# schematic.net
KiCad netlist of a schematic drawn in EAGLE
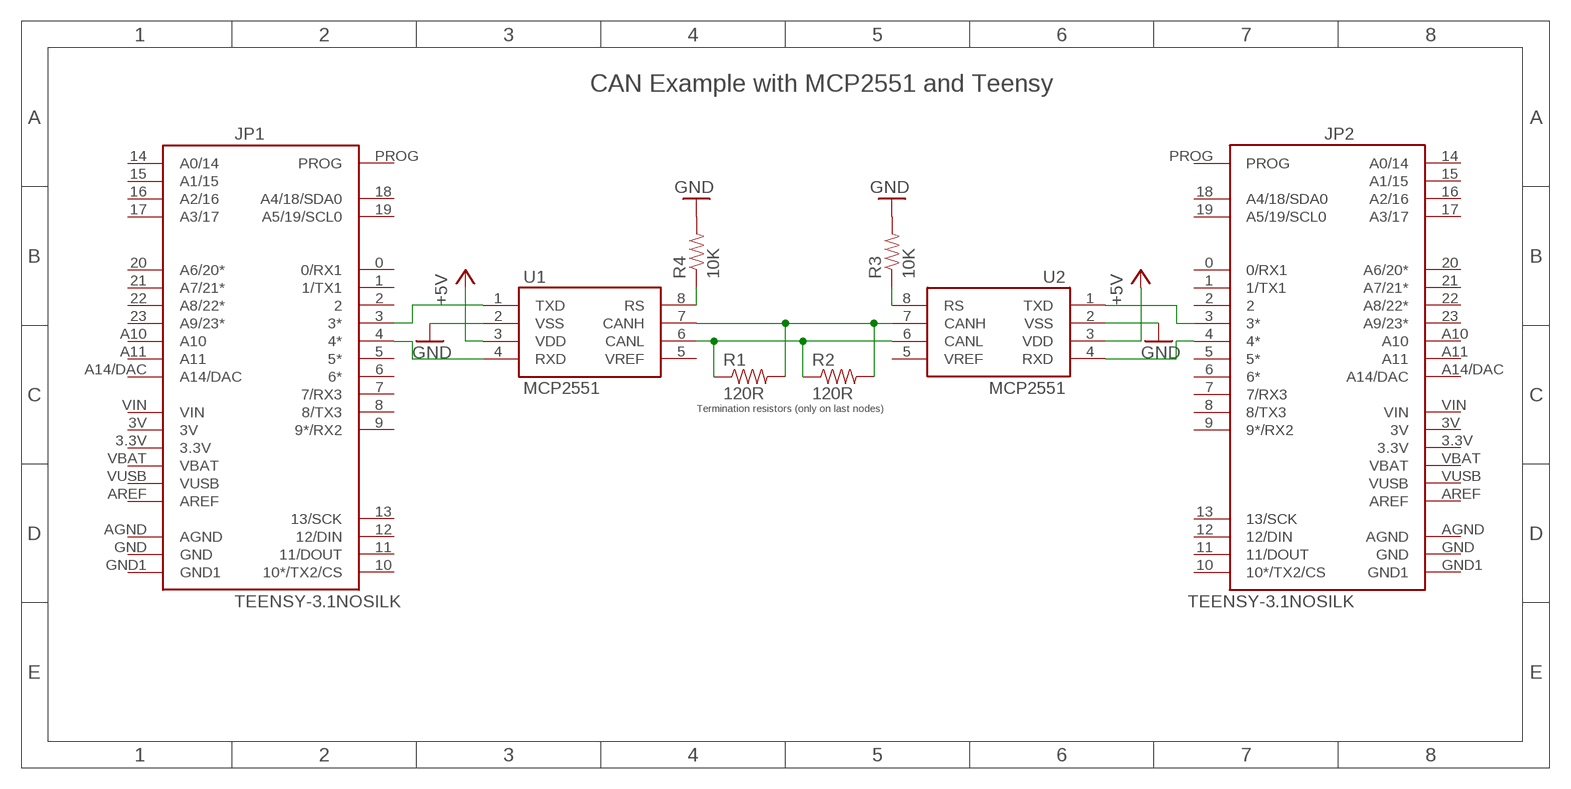
[diagram p0: schematic, sheet 1]

(export (version "E")
  (design (tool "Eeschema 10.0.6"))
  (components
    (comp (ref "JP1")
      (value "TEENSY-3.1NOSILK")
      (footprint "eagle-import:TEENSY-3.1_NOSILK")
      (libsource (lib "eagle-import") (part "TEENSY-3.1NOSILK"))
    )
    (comp (ref "JP2")
      (value "TEENSY-3.1NOSILK")
      (footprint "eagle-import:TEENSY-3.1_NOSILK")
      (libsource (lib "eagle-import") (part "TEENSY-3.1NOSILK"))
    )
    (comp (ref "R1")
      (value "120R")
      (footprint "eagle-import:0805")
      (libsource (lib "eagle-import") (part "RESISTOR0805-RES"))
    )
    (comp (ref "R2")
      (value "120R")
      (footprint "eagle-import:0805")
      (libsource (lib "eagle-import") (part "RESISTOR0805-RES"))
    )
    (comp (ref "R3")
      (value "10K")
      (footprint "eagle-import:0805")
      (libsource (lib "eagle-import") (part "RESISTOR0805-RES"))
    )
    (comp (ref "R4")
      (value "10K")
      (footprint "eagle-import:0805")
      (libsource (lib "eagle-import") (part "RESISTOR0805-RES"))
    )
    (comp (ref "U1")
      (value "MCP2551")
      (footprint "eagle-import:SO08")
      (libsource (lib "eagle-import") (part "MCP2551"))
    )
    (comp (ref "U2")
      (value "MCP2551")
      (footprint "eagle-import:SO08")
      (libsource (lib "eagle-import") (part "MCP2551"))
    )
  )
  (nets
    (net (code "1") (name "+5V") (class "Default")
      (node (ref "U1") (pin "3") (pinfunction "VDD_3") (pintype "bidirectional"))
      (node (ref "U2") (pin "3") (pinfunction "VDD_3") (pintype "bidirectional"))
    )
    (net (code "2") (name "GND") (class "Default")
      (node (ref "R3") (pin "2") (pinfunction "2_2") (pintype "passive"))
      (node (ref "R4") (pin "2") (pinfunction "2_2") (pintype "passive"))
      (node (ref "U1") (pin "2") (pinfunction "VSS_2") (pintype "bidirectional"))
      (node (ref "U2") (pin "2") (pinfunction "VSS_2") (pintype "bidirectional"))
    )
    (net (code "3") (name "Net-(JP1-3*)") (class "Default")
      (node (ref "JP1") (pin "3") (pinfunction "3*_3") (pintype "bidirectional"))
      (node (ref "U1") (pin "1") (pinfunction "TXD_1") (pintype "bidirectional"))
    )
    (net (code "4") (name "Net-(JP1-4*)") (class "Default")
      (node (ref "JP1") (pin "4") (pinfunction "4*_4") (pintype "bidirectional"))
      (node (ref "U1") (pin "4") (pinfunction "RXD_4") (pintype "bidirectional"))
    )
    (net (code "5") (name "Net-(JP2-3*)") (class "Default")
      (node (ref "JP2") (pin "3") (pinfunction "3*_3") (pintype "bidirectional"))
      (node (ref "U2") (pin "1") (pinfunction "TXD_1") (pintype "bidirectional"))
    )
    (net (code "6") (name "Net-(JP2-4*)") (class "Default")
      (node (ref "JP2") (pin "4") (pinfunction "4*_4") (pintype "bidirectional"))
      (node (ref "U2") (pin "4") (pinfunction "RXD_4") (pintype "bidirectional"))
    )
    (net (code "7") (name "Net-(U1-CANH)") (class "Default")
      (node (ref "R1") (pin "2") (pinfunction "2_2") (pintype "passive"))
      (node (ref "R2") (pin "2") (pinfunction "2_2") (pintype "passive"))
      (node (ref "U1") (pin "7") (pinfunction "CANH_7") (pintype "bidirectional"))
      (node (ref "U2") (pin "7") (pinfunction "CANH_7") (pintype "bidirectional"))
    )
    (net (code "8") (name "Net-(U1-CANL)") (class "Default")
      (node (ref "R1") (pin "1") (pinfunction "1_1") (pintype "passive"))
      (node (ref "R2") (pin "1") (pinfunction "1_1") (pintype "passive"))
      (node (ref "U1") (pin "6") (pinfunction "CANL_6") (pintype "bidirectional"))
      (node (ref "U2") (pin "6") (pinfunction "CANL_6") (pintype "bidirectional"))
    )
    (net (code "9") (name "Net-(U1-RS)") (class "Default")
      (node (ref "R4") (pin "1") (pinfunction "1_1") (pintype "passive"))
      (node (ref "U1") (pin "8") (pinfunction "RS_8") (pintype "bidirectional"))
    )
    (net (code "10") (name "Net-(U2-RS)") (class "Default")
      (node (ref "R3") (pin "1") (pinfunction "1_1") (pintype "passive"))
      (node (ref "U2") (pin "8") (pinfunction "RS_8") (pintype "bidirectional"))
    )
    (net (code "11") (name "unconnected-(JP1-0{slash}RX1-Pad0)") (class "Default")
      (node (ref "JP1") (pin "0") (pinfunction "0/RX1_0") (pintype "bidirectional"))
    )
    (net (code "12") (name "unconnected-(JP1-1{slash}TX1-Pad1)") (class "Default")
      (node (ref "JP1") (pin "1") (pinfunction "1/TX1_1") (pintype "bidirectional"))
    )
    (net (code "13") (name "unconnected-(JP1-5*-Pad5)") (class "Default")
      (node (ref "JP1") (pin "5") (pinfunction "5*_5") (pintype "bidirectional"))
    )
    (net (code "14") (name "unconnected-(JP1-6*-Pad6)") (class "Default")
      (node (ref "JP1") (pin "6") (pinfunction "6*_6") (pintype "bidirectional"))
    )
    (net (code "15") (name "unconnected-(JP1-7{slash}RX3-Pad7)") (class "Default")
      (node (ref "JP1") (pin "7") (pinfunction "7/RX3_7") (pintype "bidirectional"))
    )
    (net (code "16") (name "unconnected-(JP1-8{slash}TX3-Pad8)") (class "Default")
      (node (ref "JP1") (pin "8") (pinfunction "8/TX3_8") (pintype "bidirectional"))
    )
    (net (code "17") (name "unconnected-(JP1-9*{slash}RX2-Pad9)") (class "Default")
      (node (ref "JP1") (pin "9") (pinfunction "9*/RX2_9") (pintype "bidirectional"))
    )
    (net (code "18") (name "unconnected-(JP1-10*{slash}TX2{slash}CS-Pad10)") (class "Default")
      (node (ref "JP1") (pin "10") (pinfunction "10*/TX2/CS_10") (pintype "bidirectional"))
    )
    (net (code "19") (name "unconnected-(JP1-11{slash}DOUT-Pad11)") (class "Default")
      (node (ref "JP1") (pin "11") (pinfunction "11/DOUT_11") (pintype "bidirectional"))
    )
    (net (code "20") (name "unconnected-(JP1-12{slash}DIN-Pad12)") (class "Default")
      (node (ref "JP1") (pin "12") (pinfunction "12/DIN_12") (pintype "bidirectional"))
    )
    (net (code "21") (name "unconnected-(JP1-13{slash}SCK-Pad13)") (class "Default")
      (node (ref "JP1") (pin "13") (pinfunction "13/SCK_13") (pintype "bidirectional"))
    )
    (net (code "22") (name "unconnected-(JP1-A0{slash}14-Pad14)") (class "Default")
      (node (ref "JP1") (pin "14") (pinfunction "A0/14_14") (pintype "bidirectional"))
    )
    (net (code "23") (name "unconnected-(JP1-A1{slash}15-Pad15)") (class "Default")
      (node (ref "JP1") (pin "15") (pinfunction "A1/15_15") (pintype "bidirectional"))
    )
    (net (code "24") (name "unconnected-(JP1-A2{slash}16-Pad16)") (class "Default")
      (node (ref "JP1") (pin "16") (pinfunction "A2/16_16") (pintype "bidirectional"))
    )
    (net (code "25") (name "unconnected-(JP1-A3{slash}17-Pad17)") (class "Default")
      (node (ref "JP1") (pin "17") (pinfunction "A3/17_17") (pintype "bidirectional"))
    )
    (net (code "26") (name "unconnected-(JP1-A4{slash}18{slash}SDA0-Pad18)") (class "Default")
      (node (ref "JP1") (pin "18") (pinfunction "A4/18/SDA0_18") (pintype "bidirectional"))
    )
    (net (code "27") (name "unconnected-(JP1-A5{slash}19{slash}SCL0-Pad19)") (class "Default")
      (node (ref "JP1") (pin "19") (pinfunction "A5/19/SCL0_19") (pintype "bidirectional"))
    )
    (net (code "28") (name "unconnected-(JP1-A6{slash}20*-Pad20)") (class "Default")
      (node (ref "JP1") (pin "20") (pinfunction "A6/20*_20") (pintype "bidirectional"))
    )
    (net (code "29") (name "unconnected-(JP1-A7{slash}21*-Pad21)") (class "Default")
      (node (ref "JP1") (pin "21") (pinfunction "A7/21*_21") (pintype "bidirectional"))
    )
    (net (code "30") (name "unconnected-(JP1-A8{slash}22*-Pad22)") (class "Default")
      (node (ref "JP1") (pin "22") (pinfunction "A8/22*_22") (pintype "bidirectional"))
    )
    (net (code "31") (name "unconnected-(JP1-A9{slash}23*-Pad23)") (class "Default")
      (node (ref "JP1") (pin "23") (pinfunction "A9/23*_23") (pintype "bidirectional"))
    )
    (net (code "32") (name "unconnected-(JP1-Pad2)") (class "Default")
      (node (ref "JP1") (pin "2") (pinfunction "2_2") (pintype "bidirectional"))
    )
    (net (code "33") (name "unconnected-(JP1-Pad3.3V)") (class "Default")
      (node (ref "JP1") (pin "3.3V") (pinfunction "3.3V_3.3V") (pintype "bidirectional"))
    )
    (net (code "34") (name "unconnected-(JP1-Pad3V)") (class "Default")
      (node (ref "JP1") (pin "3V") (pinfunction "3V_3V") (pintype "bidirectional"))
    )
    (net (code "35") (name "unconnected-(JP1-PadA10)") (class "Default")
      (node (ref "JP1") (pin "A10") (pinfunction "A10_A10") (pintype "bidirectional"))
    )
    (net (code "36") (name "unconnected-(JP1-PadA11)") (class "Default")
      (node (ref "JP1") (pin "A11") (pinfunction "A11_A11") (pintype "bidirectional"))
    )
    (net (code "37") (name "unconnected-(JP1-PadA14{slash}DAC)") (class "Default")
      (node (ref "JP1") (pin "A14/DAC") (pinfunction "A14/DAC_A14/DAC") (pintype "bidirectional"))
    )
    (net (code "38") (name "unconnected-(JP1-PadAGND)") (class "Default")
      (node (ref "JP1") (pin "AGND") (pinfunction "AGND_AGND") (pintype "bidirectional"))
    )
    (net (code "39") (name "unconnected-(JP1-PadAREF)") (class "Default")
      (node (ref "JP1") (pin "AREF") (pinfunction "AREF_AREF") (pintype "bidirectional"))
    )
    (net (code "40") (name "unconnected-(JP1-PadGND)") (class "Default")
      (node (ref "JP1") (pin "GND") (pinfunction "GND_GND") (pintype "bidirectional"))
    )
    (net (code "41") (name "unconnected-(JP1-PadGND1)") (class "Default")
      (node (ref "JP1") (pin "GND1") (pinfunction "GND1_GND1") (pintype "bidirectional"))
    )
    (net (code "42") (name "unconnected-(JP1-PadPROG)") (class "Default")
      (node (ref "JP1") (pin "PROG") (pinfunction "PROG_PROG") (pintype "bidirectional"))
    )
    (net (code "43") (name "unconnected-(JP1-PadVBAT)") (class "Default")
      (node (ref "JP1") (pin "VBAT") (pinfunction "VBAT_VBAT") (pintype "bidirectional"))
    )
    (net (code "44") (name "unconnected-(JP1-PadVIN)") (class "Default")
      (node (ref "JP1") (pin "VIN") (pinfunction "VIN_VIN") (pintype "bidirectional"))
    )
    (net (code "45") (name "unconnected-(JP1-PadVUSB)") (class "Default")
      (node (ref "JP1") (pin "VUSB") (pinfunction "VUSB_VUSB") (pintype "bidirectional"))
    )
    (net (code "46") (name "unconnected-(JP2-0{slash}RX1-Pad0)") (class "Default")
      (node (ref "JP2") (pin "0") (pinfunction "0/RX1_0") (pintype "bidirectional"))
    )
    (net (code "47") (name "unconnected-(JP2-1{slash}TX1-Pad1)") (class "Default")
      (node (ref "JP2") (pin "1") (pinfunction "1/TX1_1") (pintype "bidirectional"))
    )
    (net (code "48") (name "unconnected-(JP2-5*-Pad5)") (class "Default")
      (node (ref "JP2") (pin "5") (pinfunction "5*_5") (pintype "bidirectional"))
    )
    (net (code "49") (name "unconnected-(JP2-6*-Pad6)") (class "Default")
      (node (ref "JP2") (pin "6") (pinfunction "6*_6") (pintype "bidirectional"))
    )
    (net (code "50") (name "unconnected-(JP2-7{slash}RX3-Pad7)") (class "Default")
      (node (ref "JP2") (pin "7") (pinfunction "7/RX3_7") (pintype "bidirectional"))
    )
    (net (code "51") (name "unconnected-(JP2-8{slash}TX3-Pad8)") (class "Default")
      (node (ref "JP2") (pin "8") (pinfunction "8/TX3_8") (pintype "bidirectional"))
    )
    (net (code "52") (name "unconnected-(JP2-9*{slash}RX2-Pad9)") (class "Default")
      (node (ref "JP2") (pin "9") (pinfunction "9*/RX2_9") (pintype "bidirectional"))
    )
    (net (code "53") (name "unconnected-(JP2-10*{slash}TX2{slash}CS-Pad10)") (class "Default")
      (node (ref "JP2") (pin "10") (pinfunction "10*/TX2/CS_10") (pintype "bidirectional"))
    )
    (net (code "54") (name "unconnected-(JP2-11{slash}DOUT-Pad11)") (class "Default")
      (node (ref "JP2") (pin "11") (pinfunction "11/DOUT_11") (pintype "bidirectional"))
    )
    (net (code "55") (name "unconnected-(JP2-12{slash}DIN-Pad12)") (class "Default")
      (node (ref "JP2") (pin "12") (pinfunction "12/DIN_12") (pintype "bidirectional"))
    )
    (net (code "56") (name "unconnected-(JP2-13{slash}SCK-Pad13)") (class "Default")
      (node (ref "JP2") (pin "13") (pinfunction "13/SCK_13") (pintype "bidirectional"))
    )
    (net (code "57") (name "unconnected-(JP2-A0{slash}14-Pad14)") (class "Default")
      (node (ref "JP2") (pin "14") (pinfunction "A0/14_14") (pintype "bidirectional"))
    )
    (net (code "58") (name "unconnected-(JP2-A1{slash}15-Pad15)") (class "Default")
      (node (ref "JP2") (pin "15") (pinfunction "A1/15_15") (pintype "bidirectional"))
    )
    (net (code "59") (name "unconnected-(JP2-A2{slash}16-Pad16)") (class "Default")
      (node (ref "JP2") (pin "16") (pinfunction "A2/16_16") (pintype "bidirectional"))
    )
    (net (code "60") (name "unconnected-(JP2-A3{slash}17-Pad17)") (class "Default")
      (node (ref "JP2") (pin "17") (pinfunction "A3/17_17") (pintype "bidirectional"))
    )
    (net (code "61") (name "unconnected-(JP2-A4{slash}18{slash}SDA0-Pad18)") (class "Default")
      (node (ref "JP2") (pin "18") (pinfunction "A4/18/SDA0_18") (pintype "bidirectional"))
    )
    (net (code "62") (name "unconnected-(JP2-A5{slash}19{slash}SCL0-Pad19)") (class "Default")
      (node (ref "JP2") (pin "19") (pinfunction "A5/19/SCL0_19") (pintype "bidirectional"))
    )
    (net (code "63") (name "unconnected-(JP2-A6{slash}20*-Pad20)") (class "Default")
      (node (ref "JP2") (pin "20") (pinfunction "A6/20*_20") (pintype "bidirectional"))
    )
    (net (code "64") (name "unconnected-(JP2-A7{slash}21*-Pad21)") (class "Default")
      (node (ref "JP2") (pin "21") (pinfunction "A7/21*_21") (pintype "bidirectional"))
    )
    (net (code "65") (name "unconnected-(JP2-A8{slash}22*-Pad22)") (class "Default")
      (node (ref "JP2") (pin "22") (pinfunction "A8/22*_22") (pintype "bidirectional"))
    )
    (net (code "66") (name "unconnected-(JP2-A9{slash}23*-Pad23)") (class "Default")
      (node (ref "JP2") (pin "23") (pinfunction "A9/23*_23") (pintype "bidirectional"))
    )
    (net (code "67") (name "unconnected-(JP2-Pad2)") (class "Default")
      (node (ref "JP2") (pin "2") (pinfunction "2_2") (pintype "bidirectional"))
    )
    (net (code "68") (name "unconnected-(JP2-Pad3.3V)") (class "Default")
      (node (ref "JP2") (pin "3.3V") (pinfunction "3.3V_3.3V") (pintype "bidirectional"))
    )
    (net (code "69") (name "unconnected-(JP2-Pad3V)") (class "Default")
      (node (ref "JP2") (pin "3V") (pinfunction "3V_3V") (pintype "bidirectional"))
    )
    (net (code "70") (name "unconnected-(JP2-PadA10)") (class "Default")
      (node (ref "JP2") (pin "A10") (pinfunction "A10_A10") (pintype "bidirectional"))
    )
    (net (code "71") (name "unconnected-(JP2-PadA11)") (class "Default")
      (node (ref "JP2") (pin "A11") (pinfunction "A11_A11") (pintype "bidirectional"))
    )
    (net (code "72") (name "unconnected-(JP2-PadA14{slash}DAC)") (class "Default")
      (node (ref "JP2") (pin "A14/DAC") (pinfunction "A14/DAC_A14/DAC") (pintype "bidirectional"))
    )
    (net (code "73") (name "unconnected-(JP2-PadAGND)") (class "Default")
      (node (ref "JP2") (pin "AGND") (pinfunction "AGND_AGND") (pintype "bidirectional"))
    )
    (net (code "74") (name "unconnected-(JP2-PadAREF)") (class "Default")
      (node (ref "JP2") (pin "AREF") (pinfunction "AREF_AREF") (pintype "bidirectional"))
    )
    (net (code "75") (name "unconnected-(JP2-PadGND)") (class "Default")
      (node (ref "JP2") (pin "GND") (pinfunction "GND_GND") (pintype "bidirectional"))
    )
    (net (code "76") (name "unconnected-(JP2-PadGND1)") (class "Default")
      (node (ref "JP2") (pin "GND1") (pinfunction "GND1_GND1") (pintype "bidirectional"))
    )
    (net (code "77") (name "unconnected-(JP2-PadPROG)") (class "Default")
      (node (ref "JP2") (pin "PROG") (pinfunction "PROG_PROG") (pintype "bidirectional"))
    )
    (net (code "78") (name "unconnected-(JP2-PadVBAT)") (class "Default")
      (node (ref "JP2") (pin "VBAT") (pinfunction "VBAT_VBAT") (pintype "bidirectional"))
    )
    (net (code "79") (name "unconnected-(JP2-PadVIN)") (class "Default")
      (node (ref "JP2") (pin "VIN") (pinfunction "VIN_VIN") (pintype "bidirectional"))
    )
    (net (code "80") (name "unconnected-(JP2-PadVUSB)") (class "Default")
      (node (ref "JP2") (pin "VUSB") (pinfunction "VUSB_VUSB") (pintype "bidirectional"))
    )
    (net (code "81") (name "unconnected-(U1-VREF-Pad5)") (class "Default")
      (node (ref "U1") (pin "5") (pinfunction "VREF_5") (pintype "bidirectional"))
    )
    (net (code "82") (name "unconnected-(U2-VREF-Pad5)") (class "Default")
      (node (ref "U2") (pin "5") (pinfunction "VREF_5") (pintype "bidirectional"))
    )
  )
)
